# PIN_MOUNT_J002607C.net
KiCad netlist of a schematic drawn in EAGLE
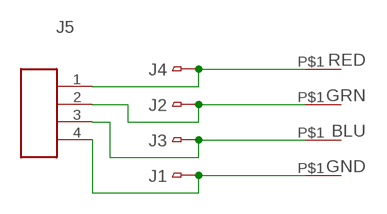
[diagram p0: schematic, sheet 1]

(export (version "E")
  (design (tool "Eeschema 10.0.6"))
  (components
    (comp (ref "BLU")
      (value "CON10851")
      (footprint "eagle-import:0851_SPRINGPIN")
      (libsource (lib "eagle-import") (part "CON10851"))
    )
    (comp (ref "GND")
      (value "CON10851")
      (footprint "eagle-import:0851_SPRINGPIN")
      (libsource (lib "eagle-import") (part "CON10851"))
    )
    (comp (ref "GRN")
      (value "CON10851")
      (footprint "eagle-import:0851_SPRINGPIN")
      (libsource (lib "eagle-import") (part "CON10851"))
    )
    (comp (ref "J1")
      (value "PADPAD_040")
      (footprint "eagle-import:PAD_040")
      (libsource (lib "eagle-import") (part "PADPAD_040"))
    )
    (comp (ref "J2")
      (value "PADPAD_040")
      (footprint "eagle-import:PAD_040")
      (libsource (lib "eagle-import") (part "PADPAD_040"))
    )
    (comp (ref "J3")
      (value "PADPAD_040")
      (footprint "eagle-import:PAD_040")
      (libsource (lib "eagle-import") (part "PADPAD_040"))
    )
    (comp (ref "J4")
      (value "PADPAD_040")
      (footprint "eagle-import:PAD_040")
      (libsource (lib "eagle-import") (part "PADPAD_040"))
    )
    (comp (ref "J5")
      (value "CON4DF13-4-TH")
      (footprint "eagle-import:DF13-4-TH")
      (libsource (lib "eagle-import") (part "CON4DF13-4-TH"))
    )
    (comp (ref "RED")
      (value "CON10851")
      (footprint "eagle-import:0851_SPRINGPIN")
      (libsource (lib "eagle-import") (part "CON10851"))
    )
  )
  (nets
    (net (code "1") (name "Net-(BLU-1)") (class "Default")
      (node (ref "BLU") (pin "P$1") (pinfunction "1_P$1") (pintype "bidirectional"))
      (node (ref "J3") (pin "P$1") (pinfunction "1_P$1") (pintype "passive"))
      (node (ref "J5") (pin "3") (pinfunction "P$3_3") (pintype "bidirectional"))
    )
    (net (code "2") (name "Net-(GND-1)") (class "Default")
      (node (ref "GND") (pin "P$1") (pinfunction "1_P$1") (pintype "bidirectional"))
      (node (ref "J1") (pin "P$1") (pinfunction "1_P$1") (pintype "passive"))
      (node (ref "J5") (pin "4") (pinfunction "P$4_4") (pintype "bidirectional"))
    )
    (net (code "3") (name "Net-(GRN-1)") (class "Default")
      (node (ref "GRN") (pin "P$1") (pinfunction "1_P$1") (pintype "bidirectional"))
      (node (ref "J2") (pin "P$1") (pinfunction "1_P$1") (pintype "passive"))
      (node (ref "J5") (pin "2") (pinfunction "P$2_2") (pintype "bidirectional"))
    )
    (net (code "4") (name "Net-(J4-1)") (class "Default")
      (node (ref "J4") (pin "P$1") (pinfunction "1_P$1") (pintype "passive"))
      (node (ref "J5") (pin "1") (pinfunction "P$1_1") (pintype "bidirectional"))
      (node (ref "RED") (pin "P$1") (pinfunction "1_P$1") (pintype "bidirectional"))
    )
  )
)
